# GPS.net
KiCad netlist of a schematic drawn in Altium Designer
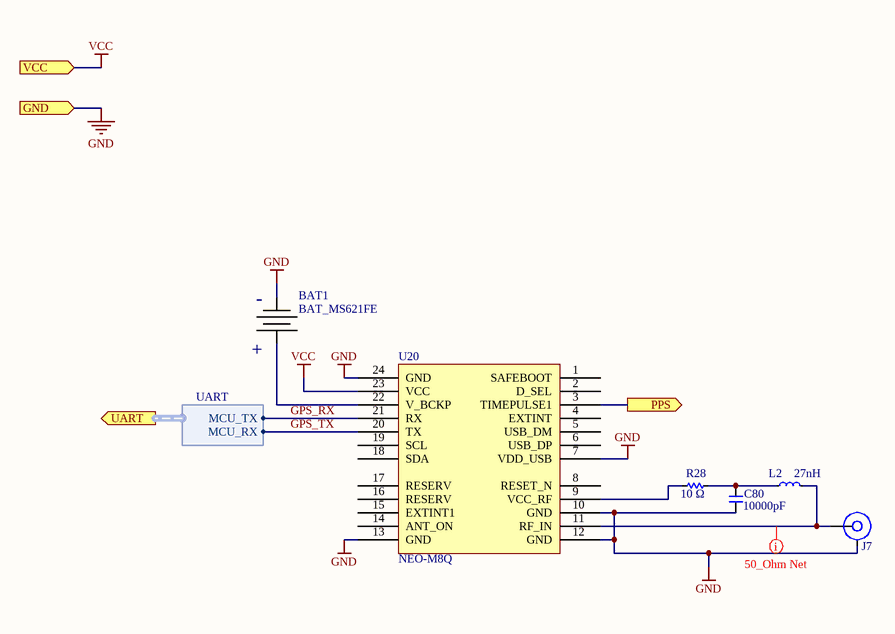
[diagram p0: GPS.SchDoc]

(export (version "E")
  (design (tool "Eeschema 10.0.6"))
  (components
    (comp (ref "BAT1")
      (value "BAT_MS621FE")
      (footprint "BATT_COINCELL_RECHARGEABLE")
      (description "MS621FE RECHARGEABLE COIN CELL BACKUP")
      (fields
        (field (name "MANUFACTURER") "Seiko Instruments")
        (field (name "MANUFACTURER PART NUMBER") "MS621FE-FL11E")
      )
      (libsource (lib "Stanford Student Space Initiative") (part "BAT_MS621FE"))
    )
    (comp (ref "C80")
      (value "490-1512-1-ND")
      (footprint "C0603")
      (description "CAP CER 0603 10000pF X7R 50V 10%")
      (fields
        (field (name "MANUFACTURER") "Murata Electronics North America")
        (field (name "CAPACITANCE (SHORTHAND)") "10000pF")
      )
      (libsource (lib "Stanford Student Space Initiative") (part "__template_cap"))
    )
    (comp (ref "J7")
      (value "SMA_SAMTEC_TH_RA")
      (footprint "SMA_SAMTEC_SMA-J-P-X-RA-TH1")
      (libsource (lib "Stanford Student Space Initiative") (part "SMA_SAMTEC_TH_RA"))
    )
    (comp (ref "L2")
      (value "490-15373-1-ND")
      (footprint "R0402")
      (description "FIXED IND 27NH 680MA 288 MOHM")
      (fields
        (field (name "INDUCTANCE") "27nH")
        (field (name "MANUFACTURER") "Murata Electronics North America")
      )
      (libsource (lib "Stanford Student Space Initiative") (part "__template_inductor"))
    )
    (comp (ref "R28")
      (value "311-10.0HRCT-ND")
      (footprint "R0603")
      (description "RES SMD 10 OHM 1% 1/10W 0603")
      (fields
        (field (name "MANUFACTURER") "Yageo")
        (field (name "RESISTANCE") "10 Ω")
        (field (name "MANUFACTURER PART NUMBER") "RC0603FR-0710RL")
      )
      (libsource (lib "Stanford Student Space Initiative") (part "__template_resistor"))
    )
    (comp (ref "U20")
      (value "NEO-M8Q")
      (footprint "NEO_M8")
      (description "Receiver GNSS 24LCC")
      (libsource (lib "Stanford Student Space Initiative") (part "NEO_M8"))
    )
  )
  (nets
    (net (code "2") (name "/GPS_RX") (class "Default")
      (node (ref "U20") (pin "21") (pinfunction "RX_21") (pintype "passive"))
    )
    (net (code "3") (name "/GPS_TX") (class "Default")
      (node (ref "U20") (pin "20") (pinfunction "TX_20") (pintype "passive"))
    )
    (net (code "4") (name "/PPS") (class "Default")
      (node (ref "U20") (pin "3") (pinfunction "TIMEPULSE1_3") (pintype "passive"))
    )
    (net (code "6") (name "GND") (class "Default")
      (node (ref "BAT1") (pin "-") (pintype "passive"))
      (node (ref "C80") (pin "1") (pintype "passive"))
      (node (ref "J7") (pin "GND") (pinfunction "GND_GND") (pintype "passive"))
      (node (ref "U20") (pin "10") (pinfunction "GND_10") (pintype "passive"))
      (node (ref "U20") (pin "12") (pinfunction "GND_12") (pintype "passive"))
      (node (ref "U20") (pin "13") (pinfunction "GND_13") (pintype "passive"))
      (node (ref "U20") (pin "24") (pinfunction "GND_24") (pintype "passive"))
      (node (ref "U20") (pin "7") (pinfunction "VDD_USB_7") (pintype "passive"))
    )
    (net (code "7") (name "Net-(C80-Pad2)") (class "Default")
      (node (ref "C80") (pin "2") (pintype "passive"))
      (node (ref "L2") (pin "1") (pintype "passive"))
      (node (ref "R28") (pin "2") (pinfunction "2_2") (pintype "passive"))
    )
    (net (code "8") (name "Net-(U20-RF_IN)") (class "Default")
      (node (ref "J7") (pin "SIG") (pinfunction "SIG_SIG") (pintype "passive"))
      (node (ref "L2") (pin "2") (pintype "passive"))
      (node (ref "U20") (pin "11") (pinfunction "RF_IN_11") (pintype "passive"))
    )
    (net (code "9") (name "Net-(U20-VCC_RF)") (class "Default")
      (node (ref "R28") (pin "1") (pinfunction "1_1") (pintype "passive"))
      (node (ref "U20") (pin "9") (pinfunction "VCC_RF_9") (pintype "passive"))
    )
    (net (code "10") (name "Net-(U20-V_BCKP)") (class "Default")
      (node (ref "BAT1") (pin "+") (pintype "passive"))
      (node (ref "U20") (pin "22") (pinfunction "V_BCKP_22") (pintype "passive"))
    )
    (net (code "11") (name "VCC") (class "Default")
      (node (ref "U20") (pin "23") (pinfunction "VCC_23") (pintype "passive"))
    )
    (net (code "12") (name "unconnected-(U20-ANT_ON-Pad14)") (class "Default")
      (node (ref "U20") (pin "14") (pinfunction "ANT_ON_14") (pintype "passive"))
    )
    (net (code "13") (name "unconnected-(U20-D_SEL-Pad2)") (class "Default")
      (node (ref "U20") (pin "2") (pinfunction "D_SEL_2") (pintype "passive"))
    )
    (net (code "14") (name "unconnected-(U20-EXTINT-Pad4)") (class "Default")
      (node (ref "U20") (pin "4") (pinfunction "EXTINT_4") (pintype "passive"))
    )
    (net (code "15") (name "unconnected-(U20-EXTINT1-Pad15)") (class "Default")
      (node (ref "U20") (pin "15") (pinfunction "EXTINT1_15") (pintype "passive"))
    )
    (net (code "16") (name "unconnected-(U20-RESERV-Pad16)") (class "Default")
      (node (ref "U20") (pin "16") (pinfunction "RESERV_16") (pintype "passive"))
    )
    (net (code "17") (name "unconnected-(U20-RESERV-Pad17)") (class "Default")
      (node (ref "U20") (pin "17") (pinfunction "RESERV_17") (pintype "passive"))
    )
    (net (code "18") (name "unconnected-(U20-RESET_N-Pad8)") (class "Default")
      (node (ref "U20") (pin "8") (pinfunction "RESET_N_8") (pintype "passive"))
    )
    (net (code "19") (name "unconnected-(U20-SAFEBOOT-Pad1)") (class "Default")
      (node (ref "U20") (pin "1") (pinfunction "SAFEBOOT_1") (pintype "passive"))
    )
    (net (code "20") (name "unconnected-(U20-SCL-Pad19)") (class "Default")
      (node (ref "U20") (pin "19") (pinfunction "SCL_19") (pintype "passive"))
    )
    (net (code "21") (name "unconnected-(U20-SDA-Pad18)") (class "Default")
      (node (ref "U20") (pin "18") (pinfunction "SDA_18") (pintype "passive"))
    )
    (net (code "22") (name "unconnected-(U20-USB_DM-Pad5)") (class "Default")
      (node (ref "U20") (pin "5") (pinfunction "USB_DM_5") (pintype "passive"))
    )
    (net (code "23") (name "unconnected-(U20-USB_DP-Pad6)") (class "Default")
      (node (ref "U20") (pin "6") (pinfunction "USB_DP_6") (pintype "passive"))
    )
  )
)
